# pic24rgbrnd01-r1.net
KiCad netlist of a schematic drawn in EAGLE
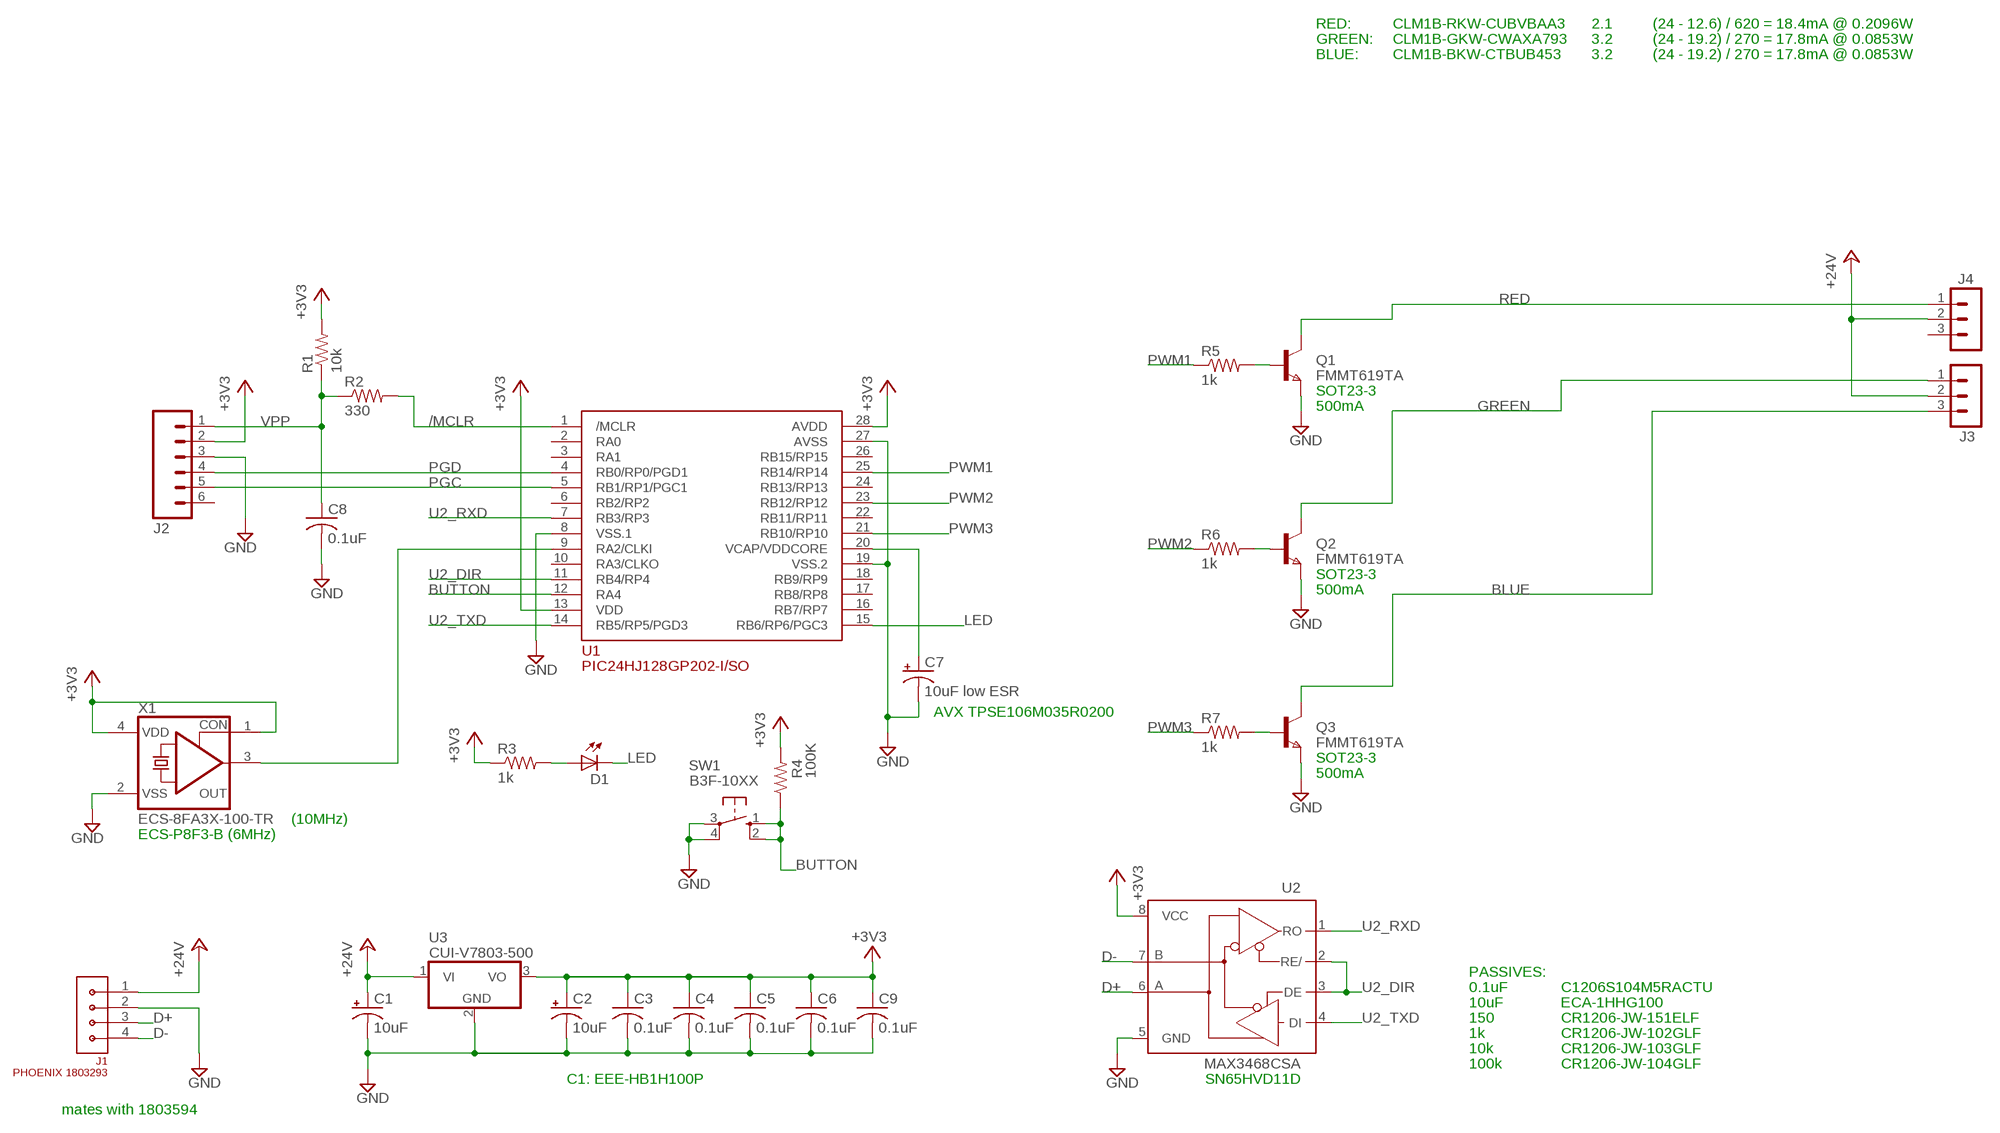
[diagram p0: schematic, sheet 1]

(export (version "E")
  (design (tool "Eeschema 10.0.6"))
  (components
    (comp (ref "C1")
      (value "10uF")
      (footprint "eagle-import:PANASONIC_D")
      (libsource (lib "eagle-import") (part "CPOL-USD"))
    )
    (comp (ref "C2")
      (value "10uF")
      (footprint "eagle-import:PANASONIC_D")
      (libsource (lib "eagle-import") (part "CPOL-USD"))
    )
    (comp (ref "C3")
      (value "0.1uF")
      (footprint "eagle-import:C1206")
      (libsource (lib "eagle-import") (part "C-USC1206"))
    )
    (comp (ref "C4")
      (value "0.1uF")
      (footprint "eagle-import:C1206")
      (libsource (lib "eagle-import") (part "C-USC1206"))
    )
    (comp (ref "C5")
      (value "0.1uF")
      (footprint "eagle-import:C1206")
      (libsource (lib "eagle-import") (part "C-USC1206"))
    )
    (comp (ref "C6")
      (value "0.1uF")
      (footprint "eagle-import:C1206")
      (libsource (lib "eagle-import") (part "C-USC1206"))
    )
    (comp (ref "C7")
      (value "10uF low ESR")
      (footprint "eagle-import:D_7343-31R")
      (libsource (lib "eagle-import") (part "CPOL-USD/7343-31R"))
    )
    (comp (ref "C8")
      (value "0.1uF")
      (footprint "eagle-import:C1206")
      (libsource (lib "eagle-import") (part "C-USC1206"))
    )
    (comp (ref "C9")
      (value "0.1uF")
      (footprint "eagle-import:C1206")
      (libsource (lib "eagle-import") (part "C-USC1206"))
    )
    (comp (ref "D1")
      (value "LED3MM")
      (footprint "eagle-import:LED3MM")
      (libsource (lib "eagle-import") (part "LED3MM"))
    )
    (comp (ref "J1")
      (value "PHOENIX 1803293")
      (footprint "eagle-import:CON-PHOENIX-1803293-3.81-1X4")
      (libsource (lib "eagle-import") (part "CON-3.81MM-1X4-PHOENIX-1803293"))
    )
    (comp (ref "J2")
      (value "M06SIP")
      (footprint "eagle-import:1X06")
      (libsource (lib "eagle-import") (part "M06SIP"))
    )
    (comp (ref "J3")
      (value "MA03-1")
      (footprint "eagle-import:MA03-1")
      (libsource (lib "eagle-import") (part "MA03-1"))
    )
    (comp (ref "J4")
      (value "MA03-1")
      (footprint "eagle-import:MA03-1")
      (libsource (lib "eagle-import") (part "MA03-1"))
    )
    (comp (ref "Q1")
      (value "FMMT619TA")
      (footprint "eagle-import:SOT-23")
      (fields (field (name "MPN") "DSS20201L-7"))
      (libsource (lib "eagle-import") (part "NPNSOT23"))
    )
    (comp (ref "Q2")
      (value "FMMT619TA")
      (footprint "eagle-import:SOT-23")
      (fields (field (name "MPN") "DSS20201L-7"))
      (libsource (lib "eagle-import") (part "NPNSOT23"))
    )
    (comp (ref "Q3")
      (value "FMMT619TA")
      (footprint "eagle-import:SOT-23")
      (fields (field (name "MPN") "DSS20201L-7"))
      (libsource (lib "eagle-import") (part "NPNSOT23"))
    )
    (comp (ref "R1")
      (value "10k")
      (footprint "eagle-import:R1206")
      (libsource (lib "eagle-import") (part "R-US_R1206"))
    )
    (comp (ref "R2")
      (value "330")
      (footprint "eagle-import:R1206")
      (libsource (lib "eagle-import") (part "R-US_R1206"))
    )
    (comp (ref "R3")
      (value "1k")
      (footprint "eagle-import:R1206")
      (libsource (lib "eagle-import") (part "R-US_R1206"))
    )
    (comp (ref "R4")
      (value "100K")
      (footprint "eagle-import:M1206")
      (libsource (lib "eagle-import") (part "R-US_M1206"))
    )
    (comp (ref "R5")
      (value "1k")
      (footprint "eagle-import:R1206")
      (libsource (lib "eagle-import") (part "R-US_R1206"))
    )
    (comp (ref "R6")
      (value "1k")
      (footprint "eagle-import:R1206")
      (libsource (lib "eagle-import") (part "R-US_R1206"))
    )
    (comp (ref "R7")
      (value "1k")
      (footprint "eagle-import:R1206")
      (libsource (lib "eagle-import") (part "R-US_R1206"))
    )
    (comp (ref "SW1")
      (value "B3F-10XX")
      (footprint "eagle-import:B3F-10XX")
      (libsource (lib "eagle-import") (part "10-XX"))
    )
    (comp (ref "U1")
      (value "PIC24HJ128GP202-I/SO")
      (footprint "eagle-import:SO28W")
      (libsource (lib "eagle-import") (part "PIC24HJ128GP202-I/SO"))
    )
    (comp (ref "U2")
      (value "MAX3468CSA")
      (footprint "eagle-import:SO08")
      (fields (field (name "MPN") "MAX3468CSA+"))
      (libsource (lib "eagle-import") (part "MAX34SA68C"))
    )
    (comp (ref "U3")
      (value "CUI-V7803-500")
      (footprint "eagle-import:CUI-78XX-500")
      (libsource (lib "eagle-import") (part "CUI-V7803-500"))
    )
    (comp (ref "X1")
      (value "ECS-8FA3X-100-TR")
      (footprint "eagle-import:1100S")
      (libsource (lib "eagle-import") (part "CRYSTAL_RES-1100S"))
    )
  )
  (nets
    (net (code "1") (name "+3V3") (class "Default")
      (node (ref "C2") (pin "+") (pinfunction "+_+") (pintype "passive"))
      (node (ref "C3") (pin "1") (pinfunction "1_1") (pintype "passive"))
      (node (ref "C4") (pin "1") (pinfunction "1_1") (pintype "passive"))
      (node (ref "C5") (pin "1") (pinfunction "1_1") (pintype "passive"))
      (node (ref "C6") (pin "1") (pinfunction "1_1") (pintype "passive"))
      (node (ref "C9") (pin "1") (pinfunction "1_1") (pintype "passive"))
      (node (ref "J2") (pin "2") (pinfunction "2_2") (pintype "passive"))
      (node (ref "R1") (pin "2") (pinfunction "2_2") (pintype "passive"))
      (node (ref "R3") (pin "1") (pinfunction "1_1") (pintype "passive"))
      (node (ref "R4") (pin "2") (pinfunction "2_2") (pintype "passive"))
      (node (ref "U1") (pin "13") (pinfunction "VDD_13") (pintype "bidirectional"))
      (node (ref "U1") (pin "28") (pinfunction "AVDD_28") (pintype "bidirectional"))
      (node (ref "U2") (pin "8") (pinfunction "VCC_8") (pintype "power_in"))
      (node (ref "U3") (pin "3") (pinfunction "VO_3") (pintype "passive"))
      (node (ref "X1") (pin "1") (pinfunction "CON_1") (pintype "input"))
      (node (ref "X1") (pin "4") (pinfunction "VDD_4") (pintype "power_in"))
    )
    (net (code "2") (name "+24V") (class "Default")
      (node (ref "C1") (pin "+") (pinfunction "+_+") (pintype "passive"))
      (node (ref "J1") (pin "1") (pinfunction "1_1") (pintype "bidirectional"))
      (node (ref "J3") (pin "2") (pinfunction "2_2") (pintype "passive"))
      (node (ref "J4") (pin "2") (pinfunction "2_2") (pintype "passive"))
      (node (ref "U3") (pin "1") (pinfunction "VI_1") (pintype "input"))
    )
    (net (code "3") (name "/BLUE") (class "Default")
      (node (ref "J3") (pin "3") (pinfunction "3_3") (pintype "passive"))
      (node (ref "Q3") (pin "1") (pinfunction "C_1") (pintype "passive"))
    )
    (net (code "4") (name "/BUTTON") (class "Default")
      (node (ref "R4") (pin "1") (pinfunction "1_1") (pintype "passive"))
      (node (ref "SW1") (pin "1") (pinfunction "S_1") (pintype "passive"))
      (node (ref "SW1") (pin "2") (pinfunction "S1_2") (pintype "passive"))
      (node (ref "U1") (pin "12") (pinfunction "RA4_12") (pintype "bidirectional"))
    )
    (net (code "5") (name "/D+") (class "Default")
      (node (ref "J1") (pin "3") (pinfunction "3_3") (pintype "bidirectional"))
      (node (ref "U2") (pin "6") (pinfunction "A_6") (pintype "passive"))
    )
    (net (code "6") (name "/D-") (class "Default")
      (node (ref "J1") (pin "4") (pinfunction "4_4") (pintype "bidirectional"))
      (node (ref "U2") (pin "7") (pinfunction "B_7") (pintype "passive"))
    )
    (net (code "7") (name "/GREEN") (class "Default")
      (node (ref "J3") (pin "1") (pinfunction "1_1") (pintype "passive"))
      (node (ref "Q2") (pin "1") (pinfunction "C_1") (pintype "passive"))
    )
    (net (code "8") (name "/LED") (class "Default")
      (node (ref "D1") (pin "K") (pinfunction "C_K") (pintype "passive"))
      (node (ref "U1") (pin "15") (pinfunction "RB6/RP6/PGC3_15") (pintype "bidirectional"))
    )
    (net (code "9") (name "/PGC") (class "Default")
      (node (ref "J2") (pin "5") (pinfunction "5_5") (pintype "passive"))
      (node (ref "U1") (pin "5") (pinfunction "RB1/RP1/PGC1_5") (pintype "bidirectional"))
    )
    (net (code "10") (name "/PGD") (class "Default")
      (node (ref "J2") (pin "4") (pinfunction "4_4") (pintype "passive"))
      (node (ref "U1") (pin "4") (pinfunction "RB0/RP0/PGD1_4") (pintype "bidirectional"))
    )
    (net (code "11") (name "/PWM1") (class "Default")
      (node (ref "R5") (pin "1") (pinfunction "1_1") (pintype "passive"))
      (node (ref "U1") (pin "25") (pinfunction "RB14/RP14_25") (pintype "bidirectional"))
    )
    (net (code "12") (name "/PWM2") (class "Default")
      (node (ref "R6") (pin "1") (pinfunction "1_1") (pintype "passive"))
      (node (ref "U1") (pin "23") (pinfunction "RB12/RP12_23") (pintype "bidirectional"))
    )
    (net (code "13") (name "/PWM3") (class "Default")
      (node (ref "R7") (pin "1") (pinfunction "1_1") (pintype "passive"))
      (node (ref "U1") (pin "21") (pinfunction "RB10/RP10_21") (pintype "bidirectional"))
    )
    (net (code "14") (name "/RED") (class "Default")
      (node (ref "J4") (pin "1") (pinfunction "1_1") (pintype "passive"))
      (node (ref "Q1") (pin "1") (pinfunction "C_1") (pintype "passive"))
    )
    (net (code "15") (name "/U2_DIR") (class "Default")
      (node (ref "U1") (pin "11") (pinfunction "RB4/RP4_11") (pintype "bidirectional"))
      (node (ref "U2") (pin "2") (pinfunction "RE/_2") (pintype "input"))
      (node (ref "U2") (pin "3") (pinfunction "DE_3") (pintype "input"))
    )
    (net (code "16") (name "/U2_RXD") (class "Default")
      (node (ref "U1") (pin "7") (pinfunction "RB3/RP3_7") (pintype "bidirectional"))
      (node (ref "U2") (pin "1") (pinfunction "RO_1") (pintype "output"))
    )
    (net (code "17") (name "/U2_TXD") (class "Default")
      (node (ref "U1") (pin "14") (pinfunction "RB5/RP5/PGD3_14") (pintype "bidirectional"))
      (node (ref "U2") (pin "4") (pinfunction "DI_4") (pintype "input"))
    )
    (net (code "18") (name "/VPP") (class "Default")
      (node (ref "C8") (pin "1") (pinfunction "1_1") (pintype "passive"))
      (node (ref "J2") (pin "1") (pinfunction "1_1") (pintype "passive"))
      (node (ref "R1") (pin "1") (pinfunction "1_1") (pintype "passive"))
      (node (ref "R2") (pin "1") (pinfunction "1_1") (pintype "passive"))
    )
    (net (code "19") (name "/{slash}MCLR") (class "Default")
      (node (ref "R2") (pin "2") (pinfunction "2_2") (pintype "passive"))
      (node (ref "U1") (pin "1") (pinfunction "/MCLR_1") (pintype "bidirectional"))
    )
    (net (code "20") (name "GND") (class "Default")
      (node (ref "C1") (pin "-") (pinfunction "-_-") (pintype "passive"))
      (node (ref "C2") (pin "-") (pinfunction "-_-") (pintype "passive"))
      (node (ref "C3") (pin "2") (pinfunction "2_2") (pintype "passive"))
      (node (ref "C4") (pin "2") (pinfunction "2_2") (pintype "passive"))
      (node (ref "C5") (pin "2") (pinfunction "2_2") (pintype "passive"))
      (node (ref "C6") (pin "2") (pinfunction "2_2") (pintype "passive"))
      (node (ref "C7") (pin "-") (pinfunction "-_-") (pintype "passive"))
      (node (ref "C8") (pin "2") (pinfunction "2_2") (pintype "passive"))
      (node (ref "C9") (pin "2") (pinfunction "2_2") (pintype "passive"))
      (node (ref "J1") (pin "2") (pinfunction "2_2") (pintype "bidirectional"))
      (node (ref "J2") (pin "3") (pinfunction "3_3") (pintype "passive"))
      (node (ref "Q1") (pin "2") (pinfunction "E_2") (pintype "passive"))
      (node (ref "Q2") (pin "2") (pinfunction "E_2") (pintype "passive"))
      (node (ref "Q3") (pin "2") (pinfunction "E_2") (pintype "passive"))
      (node (ref "SW1") (pin "3") (pinfunction "P_3") (pintype "passive"))
      (node (ref "SW1") (pin "4") (pinfunction "P1_4") (pintype "passive"))
      (node (ref "U1") (pin "19") (pinfunction "VSS.2_19") (pintype "bidirectional"))
      (node (ref "U1") (pin "27") (pinfunction "AVSS_27") (pintype "bidirectional"))
      (node (ref "U1") (pin "8") (pinfunction "VSS.1_8") (pintype "bidirectional"))
      (node (ref "U2") (pin "5") (pinfunction "GND_5") (pintype "power_in"))
      (node (ref "U3") (pin "2") (pinfunction "GND_2") (pintype "passive"))
      (node (ref "X1") (pin "2") (pinfunction "VSS_2") (pintype "power_in"))
    )
    (net (code "21") (name "Net-(D1-PadA)") (class "Default")
      (node (ref "D1") (pin "A") (pinfunction "A_A") (pintype "passive"))
      (node (ref "R3") (pin "2") (pinfunction "2_2") (pintype "passive"))
    )
    (net (code "22") (name "Net-(Q1-B)") (class "Default")
      (node (ref "Q1") (pin "3") (pinfunction "B_3") (pintype "passive"))
      (node (ref "R5") (pin "2") (pinfunction "2_2") (pintype "passive"))
    )
    (net (code "23") (name "Net-(Q2-B)") (class "Default")
      (node (ref "Q2") (pin "3") (pinfunction "B_3") (pintype "passive"))
      (node (ref "R6") (pin "2") (pinfunction "2_2") (pintype "passive"))
    )
    (net (code "24") (name "Net-(Q3-B)") (class "Default")
      (node (ref "Q3") (pin "3") (pinfunction "B_3") (pintype "passive"))
      (node (ref "R7") (pin "2") (pinfunction "2_2") (pintype "passive"))
    )
    (net (code "25") (name "Net-(U1-RA2{slash}CLKI)") (class "Default")
      (node (ref "U1") (pin "9") (pinfunction "RA2/CLKI_9") (pintype "bidirectional"))
      (node (ref "X1") (pin "3") (pinfunction "OUT_3") (pintype "output"))
    )
    (net (code "26") (name "Net-(U1-VCAP{slash}VDDCORE)") (class "Default")
      (node (ref "C7") (pin "+") (pinfunction "+_+") (pintype "passive"))
      (node (ref "U1") (pin "20") (pinfunction "VCAP/VDDCORE_20") (pintype "bidirectional"))
    )
    (net (code "27") (name "unconnected-(J2-Pad6)") (class "Default")
      (node (ref "J2") (pin "6") (pinfunction "6_6") (pintype "passive"))
    )
    (net (code "28") (name "unconnected-(J4-Pad3)") (class "Default")
      (node (ref "J4") (pin "3") (pinfunction "3_3") (pintype "passive"))
    )
    (net (code "29") (name "unconnected-(U1-RA0-Pad2)") (class "Default")
      (node (ref "U1") (pin "2") (pinfunction "RA0_2") (pintype "bidirectional"))
    )
    (net (code "30") (name "unconnected-(U1-RA1-Pad3)") (class "Default")
      (node (ref "U1") (pin "3") (pinfunction "RA1_3") (pintype "bidirectional"))
    )
    (net (code "31") (name "unconnected-(U1-RA3{slash}CLKO-Pad10)") (class "Default")
      (node (ref "U1") (pin "10") (pinfunction "RA3/CLKO_10") (pintype "bidirectional"))
    )
    (net (code "32") (name "unconnected-(U1-RB2{slash}RP2-Pad6)") (class "Default")
      (node (ref "U1") (pin "6") (pinfunction "RB2/RP2_6") (pintype "bidirectional"))
    )
    (net (code "33") (name "unconnected-(U1-RB7{slash}RP7-Pad16)") (class "Default")
      (node (ref "U1") (pin "16") (pinfunction "RB7/RP7_16") (pintype "bidirectional"))
    )
    (net (code "34") (name "unconnected-(U1-RB8{slash}RP8-Pad17)") (class "Default")
      (node (ref "U1") (pin "17") (pinfunction "RB8/RP8_17") (pintype "bidirectional"))
    )
    (net (code "35") (name "unconnected-(U1-RB9{slash}RP9-Pad18)") (class "Default")
      (node (ref "U1") (pin "18") (pinfunction "RB9/RP9_18") (pintype "bidirectional"))
    )
    (net (code "36") (name "unconnected-(U1-RB11{slash}RP11-Pad22)") (class "Default")
      (node (ref "U1") (pin "22") (pinfunction "RB11/RP11_22") (pintype "bidirectional"))
    )
    (net (code "37") (name "unconnected-(U1-RB13{slash}RP13-Pad24)") (class "Default")
      (node (ref "U1") (pin "24") (pinfunction "RB13/RP13_24") (pintype "bidirectional"))
    )
    (net (code "38") (name "unconnected-(U1-RB15{slash}RP15-Pad26)") (class "Default")
      (node (ref "U1") (pin "26") (pinfunction "RB15/RP15_26") (pintype "bidirectional"))
    )
  )
)
